# Sheet1.net
KiCad netlist of a schematic drawn in Altium Designer
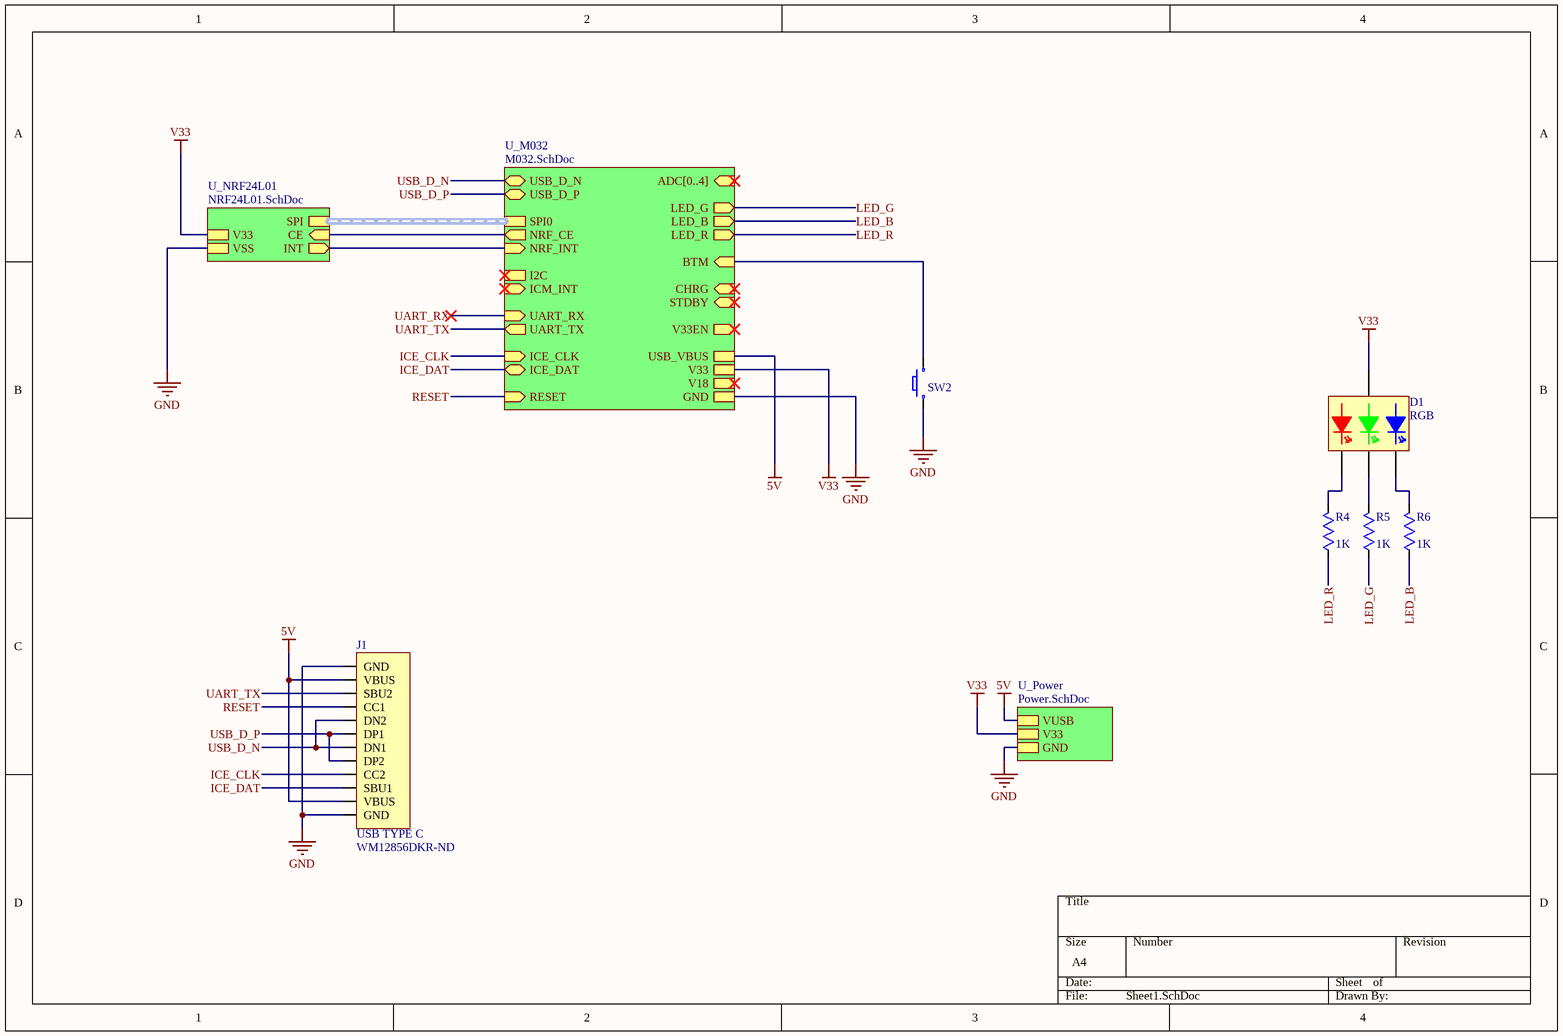
[diagram p0: Sheet1.SchDoc]

(export (version "E")
  (design (tool "Eeschema 10.0.6"))
  (components
    (comp (ref "D1") (value "RGB") (footprint "1411_LED") (libsource (lib "ZGR") (part "LED_1411")))
    (comp (ref "J1")
      (value "USB TYPE C")
      (footprint "USBC-SMD16F")
      (description "USB Shielded I/O Receptacle; Type C; Right Angle; Surface Mount; Gold over Nickel")
      (fields
        (field (name "MANUFACTURER") "Molex")
        (field (name "MANUFACTURER PART NUMBER") "105450-0101")
        (field (name "SUPPLIER PART NUMBER 1") "WM12856DKR-ND")
      )
      (libsource (lib "ZGR") (part "USB TYPE C"))
    )
    (comp (ref "R4")
      (value "1K")
      (footprint "RES_0402")
      (fields (field (name "Comment") "Res"))
      (libsource (lib "ZGR") (part "Res"))
    )
    (comp (ref "R5")
      (value "1K")
      (footprint "RES_0402")
      (fields (field (name "Comment") "Res"))
      (libsource (lib "ZGR") (part "Res"))
    )
    (comp (ref "R6")
      (value "1K")
      (footprint "RES_0402")
      (fields (field (name "Comment") "Res"))
      (libsource (lib "ZGR") (part "Res"))
    )
    (comp (ref "SW2")
      (value "SPST")
      (footprint "TACK-SW_SMD 2P 4x3mm_2")
      (libsource (lib "ZGR") (part "Switch_Button1"))
    )
  )
  (nets
    (net (code "2") (name "/BTM") (class "Default")
      (node (ref "SW2") (pin "1") (pinfunction "1_1") (pintype "passive"))
    )
    (net (code "5") (name "/ICE_CLK") (class "Default")
      (node (ref "J1") (pin "9") (pinfunction "CC2_9") (pintype "passive"))
    )
    (net (code "6") (name "/ICE_DAT") (class "Default")
      (node (ref "J1") (pin "10") (pinfunction "SBU1_10") (pintype "passive"))
    )
    (net (code "9") (name "/LED_B") (class "Default")
      (node (ref "R6") (pin "2") (pinfunction "2_2") (pintype "passive"))
    )
    (net (code "10") (name "/LED_G") (class "Default")
      (node (ref "R5") (pin "2") (pinfunction "2_2") (pintype "passive"))
    )
    (net (code "11") (name "/LED_R") (class "Default")
      (node (ref "R4") (pin "2") (pinfunction "2_2") (pintype "passive"))
    )
    (net (code "13") (name "/RESET") (class "Default")
      (node (ref "J1") (pin "4") (pinfunction "CC1_4") (pintype "passive"))
    )
    (net (code "17") (name "/UART_TX") (class "Default")
      (node (ref "J1") (pin "3") (pinfunction "SBU2_3") (pintype "passive"))
    )
    (net (code "18") (name "/USB_D_N") (class "Default")
      (node (ref "J1") (pin "5") (pinfunction "DN2_5") (pintype "passive"))
      (node (ref "J1") (pin "7") (pinfunction "DN1_7") (pintype "passive"))
    )
    (net (code "19") (name "/USB_D_P") (class "Default")
      (node (ref "J1") (pin "6") (pinfunction "DP1_6") (pintype "passive"))
      (node (ref "J1") (pin "8") (pinfunction "DP2_8") (pintype "passive"))
    )
    (net (code "22") (name "5V") (class "Default")
      (node (ref "J1") (pin "11") (pinfunction "VBUS_11") (pintype "passive"))
      (node (ref "J1") (pin "2") (pinfunction "VBUS_2") (pintype "passive"))
    )
    (net (code "23") (name "GND") (class "Default")
      (node (ref "J1") (pin "1") (pinfunction "GND_1") (pintype "passive"))
      (node (ref "J1") (pin "12") (pinfunction "GND_12") (pintype "passive"))
      (node (ref "SW2") (pin "2") (pinfunction "2_2") (pintype "passive"))
    )
    (net (code "24") (name "Net-(D1-B)") (class "Default")
      (node (ref "D1") (pin "2") (pinfunction "B_2") (pintype "passive"))
      (node (ref "R6") (pin "1") (pinfunction "1_1") (pintype "passive"))
    )
    (net (code "25") (name "Net-(D1-G)") (class "Default")
      (node (ref "D1") (pin "4") (pinfunction "G_4") (pintype "passive"))
      (node (ref "R5") (pin "1") (pinfunction "1_1") (pintype "passive"))
    )
    (net (code "26") (name "Net-(D1-R)") (class "Default")
      (node (ref "D1") (pin "3") (pinfunction "R_3") (pintype "passive"))
      (node (ref "R4") (pin "1") (pinfunction "1_1") (pintype "passive"))
    )
    (net (code "27") (name "V33") (class "Default")
      (node (ref "D1") (pin "1") (pinfunction "Anode_1") (pintype "passive"))
    )
  )
)
